# Z7_FUNCTION2.net
KiCad netlist of a schematic drawn in Altium Designer
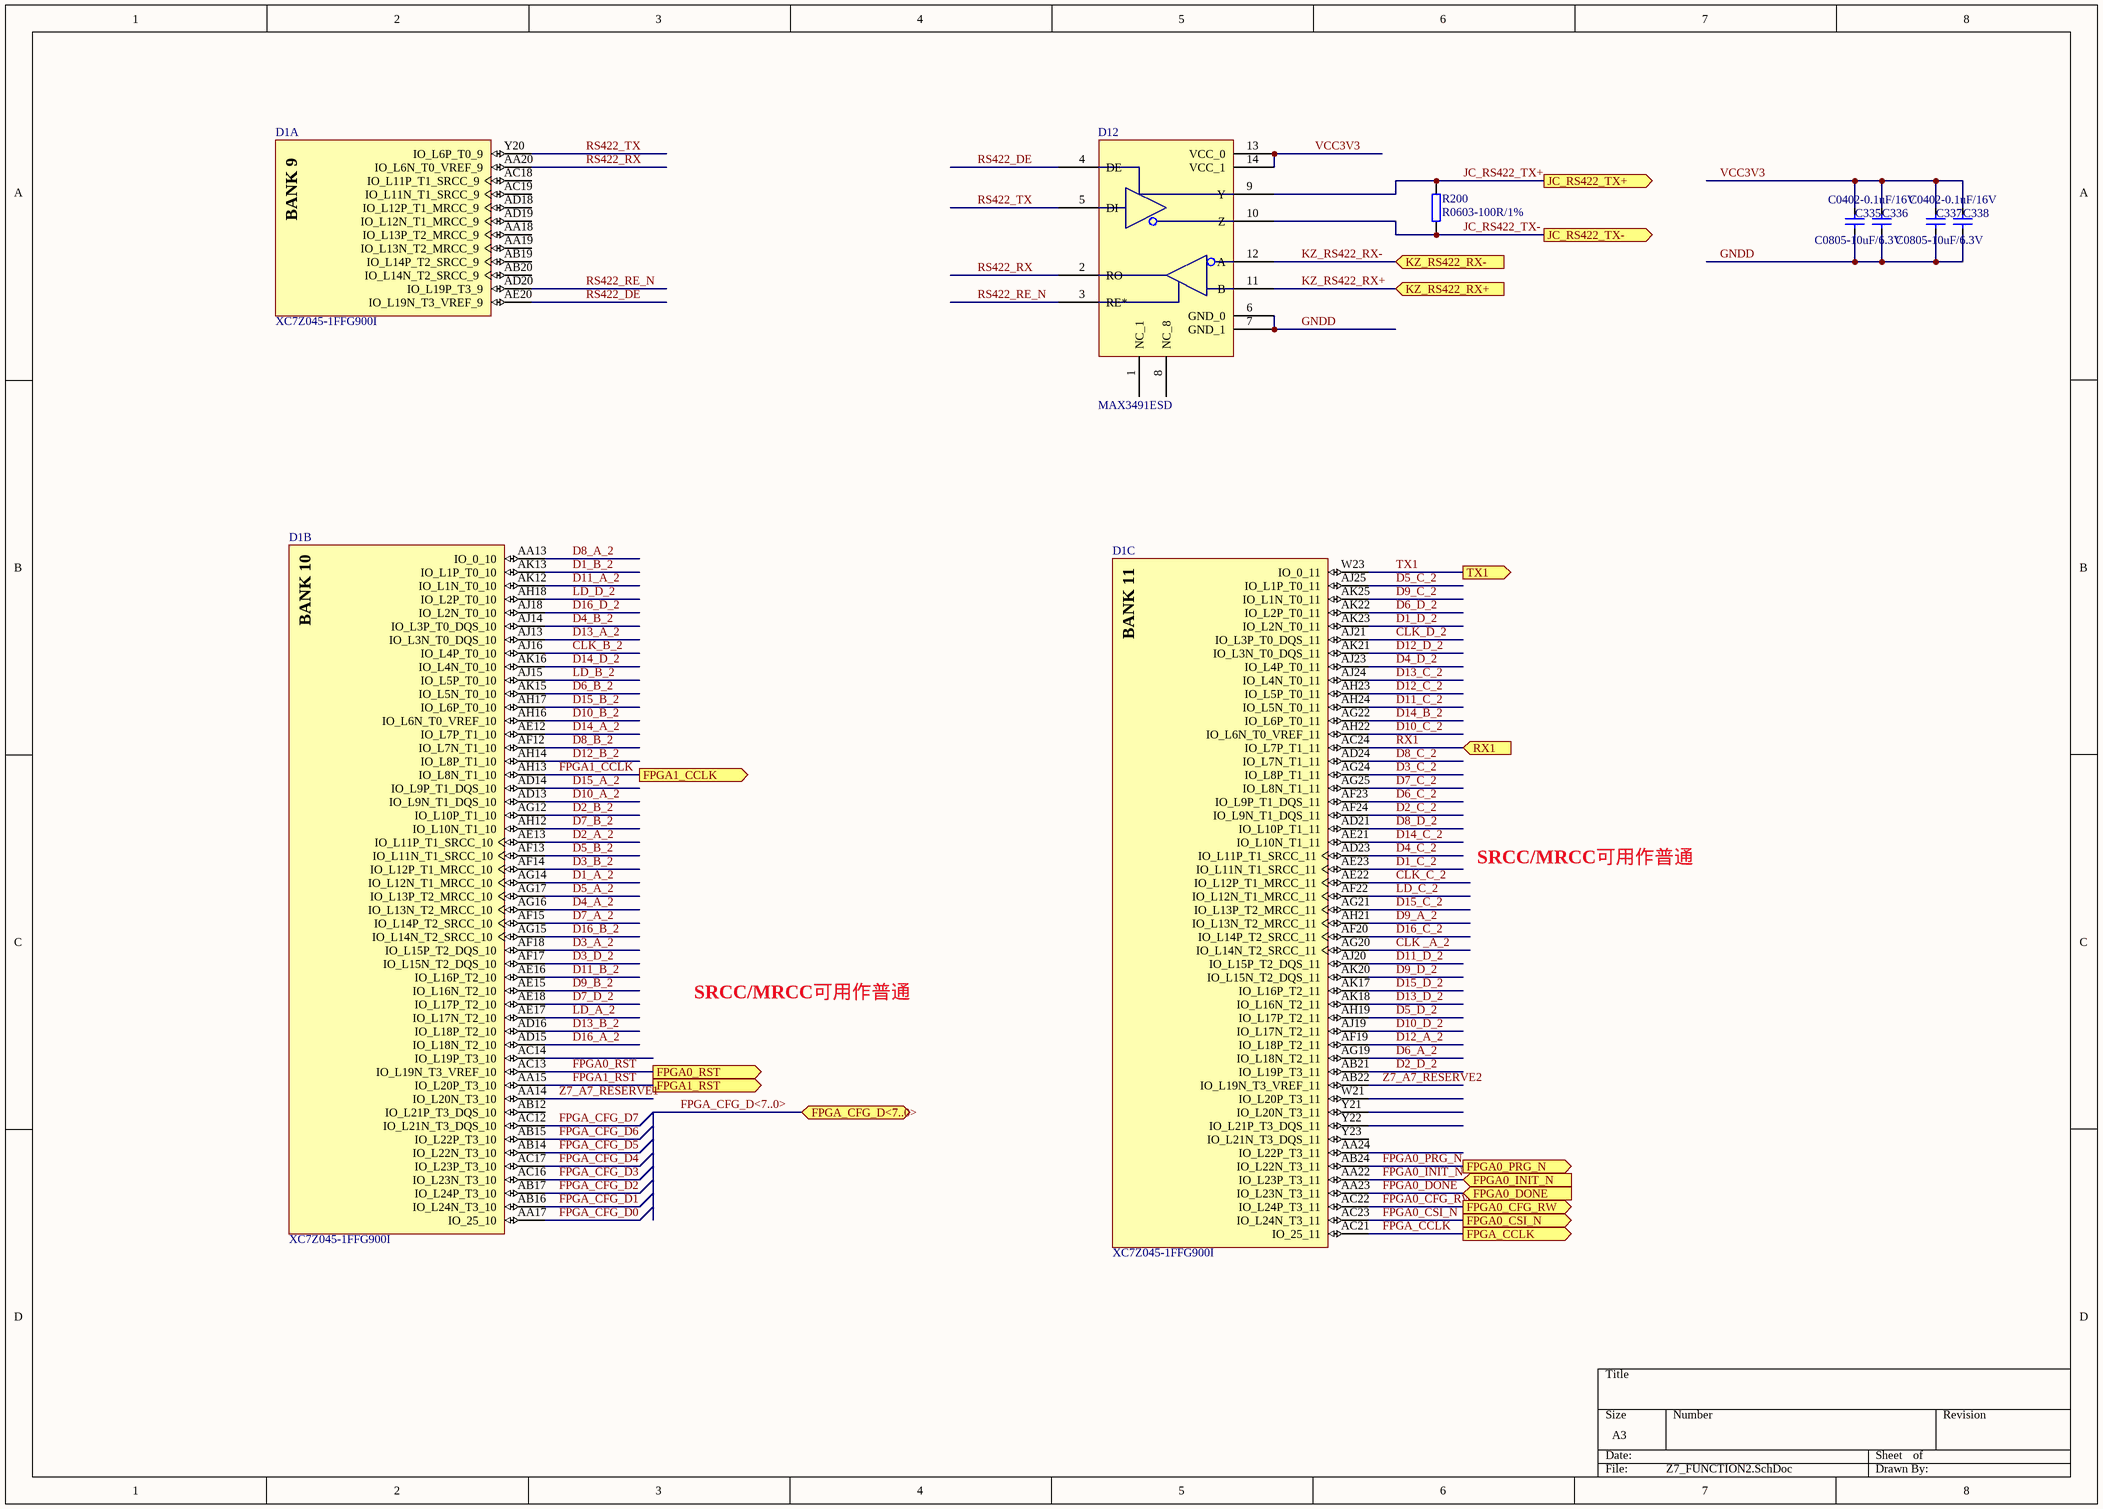
[diagram p0: Z7_FUNCTION2.SchDoc]

(export (version "E")
  (design (tool "Eeschema 10.0.6"))
  (components
    (comp (ref "C335")
      (value "C0805-10uF/6.3V")
      (footprint "C0805")
      (fields (field (name "SCHEMATIC_PART") "CAP"))
      (libsource (lib "Database_Libs1") (part "CAP"))
    )
    (comp (ref "C336")
      (value "C0402-0.1uF/16V")
      (footprint "C0402")
      (description "X7R")
      (fields (field (name "SCHEMATIC_PART") "CAP") (field (name "MANUFACTURER") "SAMSUNG"))
      (libsource (lib "Database_Libs1") (part "CAP"))
    )
    (comp (ref "C337")
      (value "C0805-10uF/6.3V")
      (footprint "C0805")
      (fields (field (name "SCHEMATIC_PART") "CAP"))
      (libsource (lib "Database_Libs1") (part "CAP"))
    )
    (comp (ref "C338")
      (value "C0402-0.1uF/16V")
      (footprint "C0402")
      (description "X7R")
      (fields (field (name "SCHEMATIC_PART") "CAP") (field (name "MANUFACTURER") "SAMSUNG"))
      (libsource (lib "Database_Libs1") (part "CAP"))
    )
    (comp (ref "D1")
      (value "XC7Z045-1FFG900I")
      (footprint "FFG900")
      (fields (field (name "GENERIC PART NUMBER") "XC7Z045") (field (name "MANUFACTURER") "Xilinx"))
      (libsource (lib "Xilinx Zynq-7000") (part "XC7Z045-1FFG900I"))
    )
    (comp (ref "D12")
      (value "MAX3491ESD")
      (footprint "SO-14")
      (libsource (lib "SCHLIB1") (part "MAX3491ESD"))
    )
    (comp (ref "R200")
      (value "R0603-100R/1%")
      (footprint "R0603")
      (fields (field (name "SCHEMATIC_PART") "RES") (field (name "MANUFACTURER") "YAGEO"))
      (libsource (lib "Database_Libs1") (part "RES"))
    )
  )
  (nets
    (net (code "2") (name "/CLK _A_2") (class "Default")
      (node (ref "D1") (pin "AG20") (pinfunction "IO_L14N_T2_SRCC_11_AG20") (pintype "bidirectional"))
    )
    (net (code "3") (name "/CLK_B_2") (class "Default")
      (node (ref "D1") (pin "AJ16") (pinfunction "IO_L4P_T0_10_AJ16") (pintype "bidirectional"))
    )
    (net (code "4") (name "/CLK_C_2") (class "Default")
      (node (ref "D1") (pin "AE22") (pinfunction "IO_L12P_T1_MRCC_11_AE22") (pintype "bidirectional"))
    )
    (net (code "5") (name "/CLK_D_2") (class "Default")
      (node (ref "D1") (pin "AJ21") (pinfunction "IO_L3P_T0_DQS_11_AJ21") (pintype "bidirectional"))
    )
    (net (code "6") (name "/D1_A_2") (class "Default")
      (node (ref "D1") (pin "AG14") (pinfunction "IO_L12N_T1_MRCC_10_AG14") (pintype "bidirectional"))
    )
    (net (code "7") (name "/D1_B_2") (class "Default")
      (node (ref "D1") (pin "AK13") (pinfunction "IO_L1P_T0_10_AK13") (pintype "bidirectional"))
    )
    (net (code "8") (name "/D1_C_2") (class "Default")
      (node (ref "D1") (pin "AE23") (pinfunction "IO_L11N_T1_SRCC_11_AE23") (pintype "bidirectional"))
    )
    (net (code "9") (name "/D1_D_2") (class "Default")
      (node (ref "D1") (pin "AK23") (pinfunction "IO_L2N_T0_11_AK23") (pintype "bidirectional"))
    )
    (net (code "10") (name "/D2_A_2") (class "Default")
      (node (ref "D1") (pin "AE13") (pinfunction "IO_L11P_T1_SRCC_10_AE13") (pintype "bidirectional"))
    )
    (net (code "11") (name "/D2_B_2") (class "Default")
      (node (ref "D1") (pin "AG12") (pinfunction "IO_L10P_T1_10_AG12") (pintype "bidirectional"))
    )
    (net (code "12") (name "/D2_C_2") (class "Default")
      (node (ref "D1") (pin "AF24") (pinfunction "IO_L9N_T1_DQS_11_AF24") (pintype "bidirectional"))
    )
    (net (code "13") (name "/D2_D_2") (class "Default")
      (node (ref "D1") (pin "AB21") (pinfunction "IO_L19P_T3_11_AB21") (pintype "bidirectional"))
    )
    (net (code "14") (name "/D3_A_2") (class "Default")
      (node (ref "D1") (pin "AF18") (pinfunction "IO_L15P_T2_DQS_10_AF18") (pintype "bidirectional"))
    )
    (net (code "15") (name "/D3_B_2") (class "Default")
      (node (ref "D1") (pin "AF14") (pinfunction "IO_L12P_T1_MRCC_10_AF14") (pintype "bidirectional"))
    )
    (net (code "16") (name "/D3_C_2") (class "Default")
      (node (ref "D1") (pin "AG24") (pinfunction "IO_L8P_T1_11_AG24") (pintype "bidirectional"))
    )
    (net (code "17") (name "/D3_D_2") (class "Default")
      (node (ref "D1") (pin "AF17") (pinfunction "IO_L15N_T2_DQS_10_AF17") (pintype "bidirectional"))
    )
    (net (code "18") (name "/D4_A_2") (class "Default")
      (node (ref "D1") (pin "AG16") (pinfunction "IO_L13N_T2_MRCC_10_AG16") (pintype "bidirectional"))
    )
    (net (code "19") (name "/D4_B_2") (class "Default")
      (node (ref "D1") (pin "AJ14") (pinfunction "IO_L3P_T0_DQS_10_AJ14") (pintype "bidirectional"))
    )
    (net (code "20") (name "/D4_C_2") (class "Default")
      (node (ref "D1") (pin "AD23") (pinfunction "IO_L11P_T1_SRCC_11_AD23") (pintype "bidirectional"))
    )
    (net (code "21") (name "/D4_D_2") (class "Default")
      (node (ref "D1") (pin "AJ23") (pinfunction "IO_L4P_T0_11_AJ23") (pintype "bidirectional"))
    )
    (net (code "22") (name "/D5_A_2") (class "Default")
      (node (ref "D1") (pin "AG17") (pinfunction "IO_L13P_T2_MRCC_10_AG17") (pintype "bidirectional"))
    )
    (net (code "23") (name "/D5_B_2") (class "Default")
      (node (ref "D1") (pin "AF13") (pinfunction "IO_L11N_T1_SRCC_10_AF13") (pintype "bidirectional"))
    )
    (net (code "24") (name "/D5_C_2") (class "Default")
      (node (ref "D1") (pin "AJ25") (pinfunction "IO_L1P_T0_11_AJ25") (pintype "bidirectional"))
    )
    (net (code "25") (name "/D5_D_2") (class "Default")
      (node (ref "D1") (pin "AH19") (pinfunction "IO_L17P_T2_11_AH19") (pintype "bidirectional"))
    )
    (net (code "26") (name "/D6_A_2") (class "Default")
      (node (ref "D1") (pin "AG19") (pinfunction "IO_L18N_T2_11_AG19") (pintype "bidirectional"))
    )
    (net (code "27") (name "/D6_B_2") (class "Default")
      (node (ref "D1") (pin "AK15") (pinfunction "IO_L5N_T0_10_AK15") (pintype "bidirectional"))
    )
    (net (code "28") (name "/D6_C_2") (class "Default")
      (node (ref "D1") (pin "AF23") (pinfunction "IO_L9P_T1_DQS_11_AF23") (pintype "bidirectional"))
    )
    (net (code "29") (name "/D6_D_2") (class "Default")
      (node (ref "D1") (pin "AK22") (pinfunction "IO_L2P_T0_11_AK22") (pintype "bidirectional"))
    )
    (net (code "30") (name "/D7_A_2") (class "Default")
      (node (ref "D1") (pin "AF15") (pinfunction "IO_L14P_T2_SRCC_10_AF15") (pintype "bidirectional"))
    )
    (net (code "31") (name "/D7_B_2") (class "Default")
      (node (ref "D1") (pin "AH12") (pinfunction "IO_L10N_T1_10_AH12") (pintype "bidirectional"))
    )
    (net (code "32") (name "/D7_C_2") (class "Default")
      (node (ref "D1") (pin "AG25") (pinfunction "IO_L8N_T1_11_AG25") (pintype "bidirectional"))
    )
    (net (code "33") (name "/D7_D_2") (class "Default")
      (node (ref "D1") (pin "AE18") (pinfunction "IO_L17P_T2_10_AE18") (pintype "bidirectional"))
    )
    (net (code "34") (name "/D8_A_2") (class "Default")
      (node (ref "D1") (pin "AA13") (pinfunction "IO_0_10_AA13") (pintype "bidirectional"))
    )
    (net (code "35") (name "/D8_B_2") (class "Default")
      (node (ref "D1") (pin "AF12") (pinfunction "IO_L7N_T1_10_AF12") (pintype "bidirectional"))
    )
    (net (code "36") (name "/D8_C_2") (class "Default")
      (node (ref "D1") (pin "AD24") (pinfunction "IO_L7N_T1_11_AD24") (pintype "bidirectional"))
    )
    (net (code "37") (name "/D8_D_2") (class "Default")
      (node (ref "D1") (pin "AD21") (pinfunction "IO_L10P_T1_11_AD21") (pintype "bidirectional"))
    )
    (net (code "38") (name "/D9_A_2") (class "Default")
      (node (ref "D1") (pin "AH21") (pinfunction "IO_L13N_T2_MRCC_11_AH21") (pintype "bidirectional"))
    )
    (net (code "39") (name "/D9_B_2") (class "Default")
      (node (ref "D1") (pin "AE15") (pinfunction "IO_L16N_T2_10_AE15") (pintype "bidirectional"))
    )
    (net (code "40") (name "/D9_C_2") (class "Default")
      (node (ref "D1") (pin "AK25") (pinfunction "IO_L1N_T0_11_AK25") (pintype "bidirectional"))
    )
    (net (code "41") (name "/D9_D_2") (class "Default")
      (node (ref "D1") (pin "AK20") (pinfunction "IO_L15N_T2_DQS_11_AK20") (pintype "bidirectional"))
    )
    (net (code "42") (name "/D10_A_2") (class "Default")
      (node (ref "D1") (pin "AD13") (pinfunction "IO_L9N_T1_DQS_10_AD13") (pintype "bidirectional"))
    )
    (net (code "43") (name "/D10_B_2") (class "Default")
      (node (ref "D1") (pin "AH16") (pinfunction "IO_L6N_T0_VREF_10_AH16") (pintype "bidirectional"))
    )
    (net (code "44") (name "/D10_C_2") (class "Default")
      (node (ref "D1") (pin "AH22") (pinfunction "IO_L6N_T0_VREF_11_AH22") (pintype "bidirectional"))
    )
    (net (code "45") (name "/D10_D_2") (class "Default")
      (node (ref "D1") (pin "AJ19") (pinfunction "IO_L17N_T2_11_AJ19") (pintype "bidirectional"))
    )
    (net (code "46") (name "/D11_A_2") (class "Default")
      (node (ref "D1") (pin "AK12") (pinfunction "IO_L1N_T0_10_AK12") (pintype "bidirectional"))
    )
    (net (code "47") (name "/D11_B_2") (class "Default")
      (node (ref "D1") (pin "AE16") (pinfunction "IO_L16P_T2_10_AE16") (pintype "bidirectional"))
    )
    (net (code "48") (name "/D11_C_2") (class "Default")
      (node (ref "D1") (pin "AH24") (pinfunction "IO_L5N_T0_11_AH24") (pintype "bidirectional"))
    )
    (net (code "49") (name "/D11_D_2") (class "Default")
      (node (ref "D1") (pin "AJ20") (pinfunction "IO_L15P_T2_DQS_11_AJ20") (pintype "bidirectional"))
    )
    (net (code "50") (name "/D12_A_2") (class "Default")
      (node (ref "D1") (pin "AF19") (pinfunction "IO_L18P_T2_11_AF19") (pintype "bidirectional"))
    )
    (net (code "51") (name "/D12_B_2") (class "Default")
      (node (ref "D1") (pin "AH14") (pinfunction "IO_L8P_T1_10_AH14") (pintype "bidirectional"))
    )
    (net (code "52") (name "/D12_C_2") (class "Default")
      (node (ref "D1") (pin "AH23") (pinfunction "IO_L5P_T0_11_AH23") (pintype "bidirectional"))
    )
    (net (code "53") (name "/D12_D_2") (class "Default")
      (node (ref "D1") (pin "AK21") (pinfunction "IO_L3N_T0_DQS_11_AK21") (pintype "bidirectional"))
    )
    (net (code "54") (name "/D13_A_2") (class "Default")
      (node (ref "D1") (pin "AJ13") (pinfunction "IO_L3N_T0_DQS_10_AJ13") (pintype "bidirectional"))
    )
    (net (code "55") (name "/D13_B_2") (class "Default")
      (node (ref "D1") (pin "AD16") (pinfunction "IO_L18P_T2_10_AD16") (pintype "bidirectional"))
    )
    (net (code "56") (name "/D13_C_2") (class "Default")
      (node (ref "D1") (pin "AJ24") (pinfunction "IO_L4N_T0_11_AJ24") (pintype "bidirectional"))
    )
    (net (code "57") (name "/D13_D_2") (class "Default")
      (node (ref "D1") (pin "AK18") (pinfunction "IO_L16N_T2_11_AK18") (pintype "bidirectional"))
    )
    (net (code "58") (name "/D14_A_2") (class "Default")
      (node (ref "D1") (pin "AE12") (pinfunction "IO_L7P_T1_10_AE12") (pintype "bidirectional"))
    )
    (net (code "59") (name "/D14_B_2") (class "Default")
      (node (ref "D1") (pin "AG22") (pinfunction "IO_L6P_T0_11_AG22") (pintype "bidirectional"))
    )
    (net (code "60") (name "/D14_C_2") (class "Default")
      (node (ref "D1") (pin "AE21") (pinfunction "IO_L10N_T1_11_AE21") (pintype "bidirectional"))
    )
    (net (code "61") (name "/D14_D_2") (class "Default")
      (node (ref "D1") (pin "AK16") (pinfunction "IO_L4N_T0_10_AK16") (pintype "bidirectional"))
    )
    (net (code "62") (name "/D15_A_2") (class "Default")
      (node (ref "D1") (pin "AD14") (pinfunction "IO_L9P_T1_DQS_10_AD14") (pintype "bidirectional"))
    )
    (net (code "63") (name "/D15_B_2") (class "Default")
      (node (ref "D1") (pin "AH17") (pinfunction "IO_L6P_T0_10_AH17") (pintype "bidirectional"))
    )
    (net (code "64") (name "/D15_C_2") (class "Default")
      (node (ref "D1") (pin "AG21") (pinfunction "IO_L13P_T2_MRCC_11_AG21") (pintype "bidirectional"))
    )
    (net (code "65") (name "/D15_D_2") (class "Default")
      (node (ref "D1") (pin "AK17") (pinfunction "IO_L16P_T2_11_AK17") (pintype "bidirectional"))
    )
    (net (code "66") (name "/D16_A_2") (class "Default")
      (node (ref "D1") (pin "AD15") (pinfunction "IO_L18N_T2_10_AD15") (pintype "bidirectional"))
    )
    (net (code "67") (name "/D16_B_2") (class "Default")
      (node (ref "D1") (pin "AG15") (pinfunction "IO_L14N_T2_SRCC_10_AG15") (pintype "bidirectional"))
    )
    (net (code "68") (name "/D16_C_2") (class "Default")
      (node (ref "D1") (pin "AF20") (pinfunction "IO_L14P_T2_SRCC_11_AF20") (pintype "bidirectional"))
    )
    (net (code "69") (name "/D16_D_2") (class "Default")
      (node (ref "D1") (pin "AJ18") (pinfunction "IO_L2N_T0_10_AJ18") (pintype "bidirectional"))
    )
    (net (code "70") (name "/FPGA0_CFG_RW") (class "Default")
      (node (ref "D1") (pin "AC22") (pinfunction "IO_L24P_T3_11_AC22") (pintype "bidirectional"))
    )
    (net (code "71") (name "/FPGA0_CSI_N") (class "Default")
      (node (ref "D1") (pin "AC23") (pinfunction "IO_L24N_T3_11_AC23") (pintype "bidirectional"))
    )
    (net (code "72") (name "/FPGA0_DONE") (class "Default")
      (node (ref "D1") (pin "AA23") (pinfunction "IO_L23N_T3_11_AA23") (pintype "bidirectional"))
    )
    (net (code "73") (name "/FPGA0_INIT_N") (class "Default")
      (node (ref "D1") (pin "AA22") (pinfunction "IO_L23P_T3_11_AA22") (pintype "bidirectional"))
    )
    (net (code "74") (name "/FPGA0_PRG_N") (class "Default")
      (node (ref "D1") (pin "AB24") (pinfunction "IO_L22N_T3_11_AB24") (pintype "bidirectional"))
    )
    (net (code "75") (name "/FPGA0_RST") (class "Default")
      (node (ref "D1") (pin "AC13") (pinfunction "IO_L19N_T3_VREF_10_AC13") (pintype "bidirectional"))
    )
    (net (code "76") (name "/FPGA1_CCLK") (class "Default")
      (node (ref "D1") (pin "AH13") (pinfunction "IO_L8N_T1_10_AH13") (pintype "bidirectional"))
    )
    (net (code "77") (name "/FPGA1_RST") (class "Default")
      (node (ref "D1") (pin "AA15") (pinfunction "IO_L20P_T3_10_AA15") (pintype "bidirectional"))
    )
    (net (code "78") (name "/FPGA_CCLK") (class "Default")
      (node (ref "D1") (pin "AC21") (pinfunction "IO_25_11_AC21") (pintype "bidirectional"))
    )
    (net (code "79") (name "/FPGA_CFG_D0") (class "Default")
      (node (ref "D1") (pin "AA17") (pinfunction "IO_25_10_AA17") (pintype "bidirectional"))
    )
    (net (code "80") (name "/FPGA_CFG_D1") (class "Default")
      (node (ref "D1") (pin "AB16") (pinfunction "IO_L24N_T3_10_AB16") (pintype "bidirectional"))
    )
    (net (code "81") (name "/FPGA_CFG_D2") (class "Default")
      (node (ref "D1") (pin "AB17") (pinfunction "IO_L24P_T3_10_AB17") (pintype "bidirectional"))
    )
    (net (code "82") (name "/FPGA_CFG_D3") (class "Default")
      (node (ref "D1") (pin "AC16") (pinfunction "IO_L23N_T3_10_AC16") (pintype "bidirectional"))
    )
    (net (code "83") (name "/FPGA_CFG_D4") (class "Default")
      (node (ref "D1") (pin "AC17") (pinfunction "IO_L23P_T3_10_AC17") (pintype "bidirectional"))
    )
    (net (code "84") (name "/FPGA_CFG_D5") (class "Default")
      (node (ref "D1") (pin "AB14") (pinfunction "IO_L22N_T3_10_AB14") (pintype "bidirectional"))
    )
    (net (code "85") (name "/FPGA_CFG_D6") (class "Default")
      (node (ref "D1") (pin "AB15") (pinfunction "IO_L22P_T3_10_AB15") (pintype "bidirectional"))
    )
    (net (code "86") (name "/FPGA_CFG_D7") (class "Default")
      (node (ref "D1") (pin "AC12") (pinfunction "IO_L21N_T3_DQS_10_AC12") (pintype "bidirectional"))
    )
    (net (code "87") (name "/GNDD") (class "Default")
      (node (ref "C335") (pin "2") (pinfunction "2_2") (pintype "passive"))
      (node (ref "C336") (pin "2") (pinfunction "2_2") (pintype "passive"))
      (node (ref "C337") (pin "2") (pinfunction "2_2") (pintype "passive"))
      (node (ref "C338") (pin "2") (pinfunction "2_2") (pintype "passive"))
      (node (ref "D12") (pin "6") (pinfunction "GND_0_6") (pintype "passive"))
      (node (ref "D12") (pin "7") (pinfunction "GND_1_7") (pintype "passive"))
    )
    (net (code "88") (name "/JC_RS422_TX+") (class "Default")
      (node (ref "D12") (pin "9") (pinfunction "Y_9") (pintype "passive"))
      (node (ref "R200") (pin "2") (pintype "passive"))
    )
    (net (code "89") (name "/JC_RS422_TX-") (class "Default")
      (node (ref "D12") (pin "10") (pinfunction "Z_10") (pintype "passive"))
      (node (ref "R200") (pin "1") (pintype "passive"))
    )
    (net (code "90") (name "/KZ_RS422_RX+") (class "Default")
      (node (ref "D12") (pin "11") (pinfunction "B_11") (pintype "passive"))
    )
    (net (code "91") (name "/KZ_RS422_RX-") (class "Default")
      (node (ref "D12") (pin "12") (pinfunction "A_12") (pintype "passive"))
    )
    (net (code "92") (name "/LD_A_2") (class "Default")
      (node (ref "D1") (pin "AE17") (pinfunction "IO_L17N_T2_10_AE17") (pintype "bidirectional"))
    )
    (net (code "93") (name "/LD_B_2") (class "Default")
      (node (ref "D1") (pin "AJ15") (pinfunction "IO_L5P_T0_10_AJ15") (pintype "bidirectional"))
    )
    (net (code "94") (name "/LD_C_2") (class "Default")
      (node (ref "D1") (pin "AF22") (pinfunction "IO_L12N_T1_MRCC_11_AF22") (pintype "bidirectional"))
    )
    (net (code "95") (name "/LD_D_2") (class "Default")
      (node (ref "D1") (pin "AH18") (pinfunction "IO_L2P_T0_10_AH18") (pintype "bidirectional"))
    )
    (net (code "96") (name "/RS422_DE") (class "Default")
      (node (ref "D1") (pin "AE20") (pinfunction "IO_L19N_T3_VREF_9_AE20") (pintype "bidirectional"))
      (node (ref "D12") (pin "4") (pinfunction "DE_4") (pintype "passive"))
    )
    (net (code "97") (name "/RS422_RE_N") (class "Default")
      (node (ref "D1") (pin "AD20") (pinfunction "IO_L19P_T3_9_AD20") (pintype "bidirectional"))
      (node (ref "D12") (pin "3") (pinfunction "RE*_3") (pintype "open_collector"))
    )
    (net (code "98") (name "/RS422_RX") (class "Default")
      (node (ref "D1") (pin "AA20") (pinfunction "IO_L6N_T0_VREF_9_AA20") (pintype "bidirectional"))
      (node (ref "D12") (pin "2") (pinfunction "RO_2") (pintype "passive"))
    )
    (net (code "99") (name "/RS422_TX") (class "Default")
      (node (ref "D1") (pin "Y20") (pinfunction "IO_L6P_T0_9_Y20") (pintype "bidirectional"))
      (node (ref "D12") (pin "5") (pinfunction "DI_5") (pintype "passive"))
    )
    (net (code "100") (name "/RX1") (class "Default")
      (node (ref "D1") (pin "AC24") (pinfunction "IO_L7P_T1_11_AC24") (pintype "bidirectional"))
    )
    (net (code "101") (name "/TX1") (class "Default")
      (node (ref "D1") (pin "W23") (pinfunction "IO_0_11_W23") (pintype "bidirectional"))
    )
    (net (code "102") (name "/VCC3V3") (class "Default")
      (node (ref "C335") (pin "1") (pinfunction "1_1") (pintype "passive"))
      (node (ref "C336") (pin "1") (pinfunction "1_1") (pintype "passive"))
      (node (ref "C337") (pin "1") (pinfunction "1_1") (pintype "passive"))
      (node (ref "C338") (pin "1") (pinfunction "1_1") (pintype "passive"))
      (node (ref "D12") (pin "13") (pinfunction "VCC_0_13") (pintype "passive"))
      (node (ref "D12") (pin "14") (pinfunction "VCC_1_14") (pintype "passive"))
    )
    (net (code "103") (name "/Z7_A7_RESERVE1") (class "Default")
      (node (ref "D1") (pin "AA14") (pinfunction "IO_L20N_T3_10_AA14") (pintype "bidirectional"))
    )
    (net (code "104") (name "/Z7_A7_RESERVE2") (class "Default")
      (node (ref "D1") (pin "AB22") (pinfunction "IO_L19N_T3_VREF_11_AB22") (pintype "bidirectional"))
    )
    (net (code "106") (name "unconnected-(D1A-IO_L11N_T1_SRCC_9-PadAC19)") (class "Default")
      (node (ref "D1") (pin "AC19") (pinfunction "IO_L11N_T1_SRCC_9_AC19") (pintype "bidirectional"))
    )
    (net (code "107") (name "unconnected-(D1A-IO_L11P_T1_SRCC_9-PadAC18)") (class "Default")
      (node (ref "D1") (pin "AC18") (pinfunction "IO_L11P_T1_SRCC_9_AC18") (pintype "bidirectional"))
    )
    (net (code "108") (name "unconnected-(D1A-IO_L12N_T1_MRCC_9-PadAD19)") (class "Default")
      (node (ref "D1") (pin "AD19") (pinfunction "IO_L12N_T1_MRCC_9_AD19") (pintype "bidirectional"))
    )
    (net (code "109") (name "unconnected-(D1A-IO_L12P_T1_MRCC_9-PadAD18)") (class "Default")
      (node (ref "D1") (pin "AD18") (pinfunction "IO_L12P_T1_MRCC_9_AD18") (pintype "bidirectional"))
    )
    (net (code "110") (name "unconnected-(D1A-IO_L13N_T2_MRCC_9-PadAA19)") (class "Default")
      (node (ref "D1") (pin "AA19") (pinfunction "IO_L13N_T2_MRCC_9_AA19") (pintype "bidirectional"))
    )
    (net (code "111") (name "unconnected-(D1A-IO_L13P_T2_MRCC_9-PadAA18)") (class "Default")
      (node (ref "D1") (pin "AA18") (pinfunction "IO_L13P_T2_MRCC_9_AA18") (pintype "bidirectional"))
    )
    (net (code "112") (name "unconnected-(D1A-IO_L14N_T2_SRCC_9-PadAB20)") (class "Default")
      (node (ref "D1") (pin "AB20") (pinfunction "IO_L14N_T2_SRCC_9_AB20") (pintype "bidirectional"))
    )
    (net (code "113") (name "unconnected-(D1A-IO_L14P_T2_SRCC_9-PadAB19)") (class "Default")
      (node (ref "D1") (pin "AB19") (pinfunction "IO_L14P_T2_SRCC_9_AB19") (pintype "bidirectional"))
    )
    (net (code "114") (name "unconnected-(D1B-IO_L19P_T3_10-PadAC14)") (class "Default")
      (node (ref "D1") (pin "AC14") (pinfunction "IO_L19P_T3_10_AC14") (pintype "bidirectional"))
    )
    (net (code "115") (name "unconnected-(D1B-IO_L21P_T3_DQS_10-PadAB12)") (class "Default")
      (node (ref "D1") (pin "AB12") (pinfunction "IO_L21P_T3_DQS_10_AB12") (pintype "bidirectional"))
    )
    (net (code "116") (name "unconnected-(D1C-IO_L20N_T3_11-PadY21)") (class "Default")
      (node (ref "D1") (pin "Y21") (pinfunction "IO_L20N_T3_11_Y21") (pintype "bidirectional"))
    )
    (net (code "117") (name "unconnected-(D1C-IO_L20P_T3_11-PadW21)") (class "Default")
      (node (ref "D1") (pin "W21") (pinfunction "IO_L20P_T3_11_W21") (pintype "bidirectional"))
    )
    (net (code "118") (name "unconnected-(D1C-IO_L21N_T3_DQS_11-PadY23)") (class "Default")
      (node (ref "D1") (pin "Y23") (pinfunction "IO_L21N_T3_DQS_11_Y23") (pintype "bidirectional"))
    )
    (net (code "119") (name "unconnected-(D1C-IO_L21P_T3_DQS_11-PadY22)") (class "Default")
      (node (ref "D1") (pin "Y22") (pinfunction "IO_L21P_T3_DQS_11_Y22") (pintype "bidirectional"))
    )
    (net (code "120") (name "unconnected-(D1C-IO_L22P_T3_11-PadAA24)") (class "Default")
      (node (ref "D1") (pin "AA24") (pinfunction "IO_L22P_T3_11_AA24") (pintype "bidirectional"))
    )
    (net (code "121") (name "unconnected-(D12-NC_1-Pad1)") (class "Default")
      (node (ref "D12") (pin "1") (pinfunction "NC_1_1") (pintype "passive"))
    )
    (net (code "122") (name "unconnected-(D12-NC_8-Pad8)") (class "Default")
      (node (ref "D12") (pin "8") (pinfunction "NC_8_8") (pintype "passive"))
    )
  )
)
